# Drives.net
KiCad netlist of a schematic drawn in Altium Designer
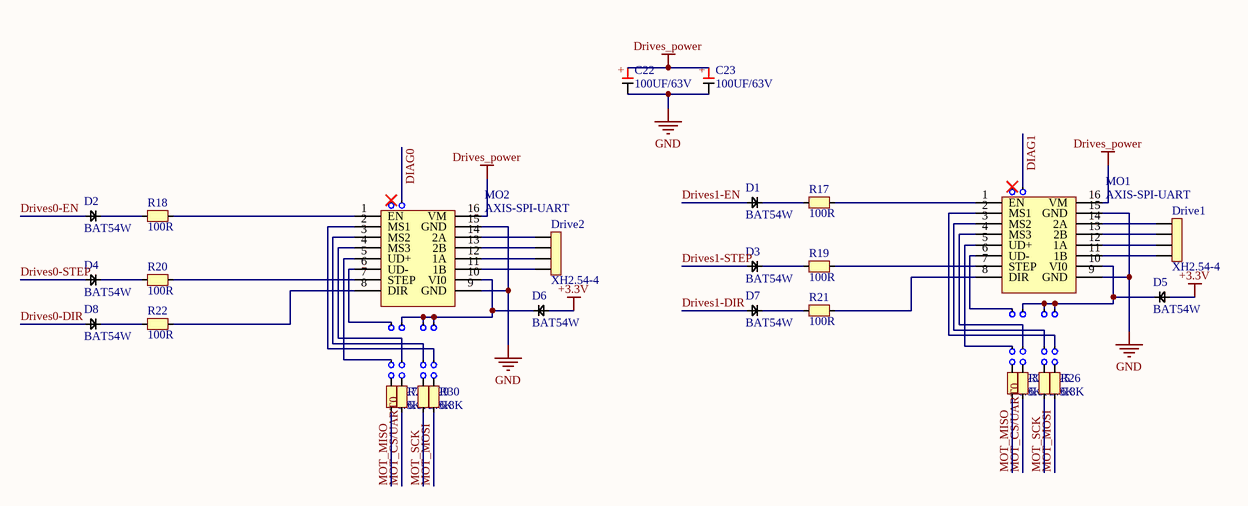
[diagram p0: Drives.SchDoc]

(export (version "E")
  (design (tool "Eeschema 10.0.6"))
  (components
    (comp (ref "C22") (value "100UF/63V") (footprint "10*10.5电解电容") (libsource (lib "jx") (part "降压电容")))
    (comp (ref "C23") (value "100UF/63V") (footprint "10*10.5电解电容") (libsource (lib "jx") (part "降压电容")))
    (comp (ref "D1")
      (value "BAT54W")
      (footprint "SOD-123")
      (description "BAT46W")
      (libsource (lib "jx") (part "Diode"))
    )
    (comp (ref "D2")
      (value "BAT54W")
      (footprint "SOD-123")
      (description "BAT46W")
      (libsource (lib "jx") (part "Diode"))
    )
    (comp (ref "D3")
      (value "BAT54W")
      (footprint "SOD-123")
      (description "BAT46W")
      (libsource (lib "jx") (part "Diode"))
    )
    (comp (ref "D4")
      (value "BAT54W")
      (footprint "SOD-123")
      (description "BAT46W")
      (libsource (lib "jx") (part "Diode"))
    )
    (comp (ref "D5")
      (value "BAT54W")
      (footprint "SOD-123")
      (description "BAT46W")
      (libsource (lib "jx") (part "Diode"))
    )
    (comp (ref "D6")
      (value "BAT54W")
      (footprint "SOD-123")
      (description "BAT46W")
      (libsource (lib "jx") (part "Diode"))
    )
    (comp (ref "D7")
      (value "BAT54W")
      (footprint "SOD-123")
      (description "BAT46W")
      (libsource (lib "jx") (part "Diode"))
    )
    (comp (ref "D8")
      (value "BAT54W")
      (footprint "SOD-123")
      (description "BAT46W")
      (libsource (lib "jx") (part "Diode"))
    )
    (comp (ref "Drive1") (value "XH2.54-4") (footprint "XH2.54-4") (libsource (lib "jx") (part "XH2.54-4")))
    (comp (ref "Drive2") (value "XH2.54-4") (footprint "XH2.54-4") (libsource (lib "jx") (part "XH2.54-4")))
    (comp (ref "MO1")
      (value "AXIS-SPI-UART")
      (footprint "AXIS-SPI-UART")
      (libsource (lib "jx") (part "AXIS-SPI-UART"))
    )
    (comp (ref "MO2")
      (value "AXIS-SPI-UART")
      (footprint "AXIS-SPI-UART")
      (libsource (lib "jx") (part "AXIS-SPI-UART"))
    )
    (comp (ref "R17") (value "100R") (footprint "0603") (libsource (lib "") (part "R_1")))
    (comp (ref "R18") (value "100R") (footprint "0603") (libsource (lib "") (part "R_1")))
    (comp (ref "R19") (value "100R") (footprint "0603") (libsource (lib "") (part "R_1")))
    (comp (ref "R20") (value "100R") (footprint "0603") (libsource (lib "") (part "R_1")))
    (comp (ref "R21") (value "100R") (footprint "0603") (libsource (lib "") (part "R_1")))
    (comp (ref "R22") (value "100R") (footprint "0603") (libsource (lib "") (part "R_1")))
    (comp (ref "R23") (value "6.8K") (footprint "0603") (libsource (lib "jx") (part "R")))
    (comp (ref "R24") (value "6.8K") (footprint "0603") (libsource (lib "jx") (part "R")))
    (comp (ref "R25") (value "6.8K") (footprint "0603") (libsource (lib "jx") (part "R")))
    (comp (ref "R26") (value "6.8K") (footprint "0603") (libsource (lib "jx") (part "R")))
    (comp (ref "R27") (value "6.8K") (footprint "0603") (libsource (lib "jx") (part "R")))
    (comp (ref "R28") (value "6.8K") (footprint "0603") (libsource (lib "jx") (part "R")))
    (comp (ref "R29") (value "6.8K") (footprint "0603") (libsource (lib "jx") (part "R")))
    (comp (ref "R30") (value "6.8K") (footprint "0603") (libsource (lib "jx") (part "R")))
  )
  (nets
    (net (code "1") (name "+3.3V") (class "Default")
      (node (ref "D5") (pin "1") (pinfunction "1_1") (pintype "passive"))
      (node (ref "D6") (pin "1") (pinfunction "1_1") (pintype "passive"))
    )
    (net (code "2") (name "/DIAG0") (class "Default")
      (node (ref "MO2") (pin "30") (pinfunction "4_30") (pintype "passive"))
    )
    (net (code "3") (name "/DIAG1") (class "Default")
      (node (ref "MO1") (pin "30") (pinfunction "4_30") (pintype "passive"))
    )
    (net (code "4") (name "/Drives0-DIR") (class "Default")
      (node (ref "D8") (pin "1") (pinfunction "1_1") (pintype "passive"))
    )
    (net (code "5") (name "/Drives0-EN") (class "Default")
      (node (ref "D2") (pin "1") (pinfunction "1_1") (pintype "passive"))
    )
    (net (code "6") (name "/Drives0-STEP") (class "Default")
      (node (ref "D4") (pin "1") (pinfunction "1_1") (pintype "passive"))
    )
    (net (code "7") (name "/Drives1-DIR") (class "Default")
      (node (ref "D7") (pin "1") (pinfunction "1_1") (pintype "passive"))
    )
    (net (code "8") (name "/Drives1-EN") (class "Default")
      (node (ref "D1") (pin "1") (pinfunction "1_1") (pintype "passive"))
    )
    (net (code "9") (name "/Drives1-STEP") (class "Default")
      (node (ref "D3") (pin "1") (pinfunction "1_1") (pintype "passive"))
    )
    (net (code "10") (name "/MOT_CS{slash}UART0") (class "Default")
      (node (ref "R24") (pin "1") (pinfunction "1_1") (pintype "passive"))
      (node (ref "R28") (pin "1") (pinfunction "1_1") (pintype "passive"))
    )
    (net (code "11") (name "/MOT_MISO") (class "Default")
      (node (ref "R23") (pin "1") (pinfunction "1_1") (pintype "passive"))
      (node (ref "R27") (pin "1") (pinfunction "1_1") (pintype "passive"))
    )
    (net (code "12") (name "/MOT_MOSI") (class "Default")
      (node (ref "R26") (pin "1") (pinfunction "1_1") (pintype "passive"))
      (node (ref "R30") (pin "1") (pinfunction "1_1") (pintype "passive"))
    )
    (net (code "13") (name "/MOT_SCK") (class "Default")
      (node (ref "R25") (pin "1") (pinfunction "1_1") (pintype "passive"))
      (node (ref "R29") (pin "1") (pinfunction "1_1") (pintype "passive"))
    )
    (net (code "14") (name "Drives_power") (class "Default")
      (node (ref "C22") (pin "1") (pinfunction "1_1") (pintype "passive"))
      (node (ref "C23") (pin "1") (pinfunction "1_1") (pintype "passive"))
      (node (ref "MO1") (pin "16") (pinfunction "VM_16") (pintype "passive"))
      (node (ref "MO2") (pin "16") (pinfunction "VM_16") (pintype "passive"))
    )
    (net (code "15") (name "GND") (class "Default")
      (node (ref "C22") (pin "2") (pinfunction "2_2") (pintype "passive"))
      (node (ref "C23") (pin "2") (pinfunction "2_2") (pintype "passive"))
      (node (ref "MO1") (pin "15") (pinfunction "GND_15") (pintype "passive"))
      (node (ref "MO1") (pin "9") (pinfunction "GND_9") (pintype "passive"))
      (node (ref "MO2") (pin "15") (pinfunction "GND_15") (pintype "passive"))
      (node (ref "MO2") (pin "9") (pinfunction "GND_9") (pintype "passive"))
    )
    (net (code "16") (name "Net-(D1-Pad2)") (class "Default")
      (node (ref "D1") (pin "2") (pinfunction "2_2") (pintype "passive"))
      (node (ref "R17") (pin "2") (pinfunction "2_2") (pintype "passive"))
    )
    (net (code "17") (name "Net-(D2-Pad2)") (class "Default")
      (node (ref "D2") (pin "2") (pinfunction "2_2") (pintype "passive"))
      (node (ref "R18") (pin "2") (pinfunction "2_2") (pintype "passive"))
    )
    (net (code "18") (name "Net-(D3-Pad2)") (class "Default")
      (node (ref "D3") (pin "2") (pinfunction "2_2") (pintype "passive"))
      (node (ref "R19") (pin "2") (pinfunction "2_2") (pintype "passive"))
    )
    (net (code "19") (name "Net-(D4-Pad2)") (class "Default")
      (node (ref "D4") (pin "2") (pinfunction "2_2") (pintype "passive"))
      (node (ref "R20") (pin "2") (pinfunction "2_2") (pintype "passive"))
    )
    (net (code "20") (name "Net-(D7-Pad2)") (class "Default")
      (node (ref "D7") (pin "2") (pinfunction "2_2") (pintype "passive"))
      (node (ref "R21") (pin "2") (pinfunction "2_2") (pintype "passive"))
    )
    (net (code "21") (name "Net-(D8-Pad2)") (class "Default")
      (node (ref "D8") (pin "2") (pinfunction "2_2") (pintype "passive"))
      (node (ref "R22") (pin "2") (pinfunction "2_2") (pintype "passive"))
    )
    (net (code "22") (name "Net-(MO1-1A)") (class "Default")
      (node (ref "Drive1") (pin "3") (pinfunction "3_3") (pintype "passive"))
      (node (ref "MO1") (pin "12") (pinfunction "1A_12") (pintype "passive"))
    )
    (net (code "23") (name "Net-(MO1-1B)") (class "Default")
      (node (ref "Drive1") (pin "4") (pinfunction "4_4") (pintype "passive"))
      (node (ref "MO1") (pin "11") (pinfunction "1B_11") (pintype "passive"))
    )
    (net (code "24") (name "Net-(MO1-2-Pad25)") (class "Default")
      (node (ref "MO1") (pin "25") (pinfunction "2_25") (pintype "passive"))
      (node (ref "R25") (pin "2") (pinfunction "2_2") (pintype "passive"))
    )
    (net (code "25") (name "Net-(MO1-2A)") (class "Default")
      (node (ref "Drive1") (pin "1") (pinfunction "1_1") (pintype "passive"))
      (node (ref "MO1") (pin "14") (pinfunction "2A_14") (pintype "passive"))
    )
    (net (code "26") (name "Net-(MO1-2B)") (class "Default")
      (node (ref "Drive1") (pin "2") (pinfunction "2_2") (pintype "passive"))
      (node (ref "MO1") (pin "13") (pinfunction "2B_13") (pintype "passive"))
    )
    (net (code "27") (name "Net-(MO1-3-Pad19)") (class "Default")
      (node (ref "MO1") (pin "19") (pinfunction "3_19") (pintype "passive"))
      (node (ref "R23") (pin "2") (pinfunction "2_2") (pintype "passive"))
    )
    (net (code "28") (name "Net-(MO1-4-Pad20)") (class "Default")
      (node (ref "MO1") (pin "20") (pinfunction "4_20") (pintype "passive"))
      (node (ref "R24") (pin "2") (pinfunction "2_2") (pintype "passive"))
    )
    (net (code "29") (name "Net-(MO1-5-Pad26)") (class "Default")
      (node (ref "MO1") (pin "26") (pinfunction "5_26") (pintype "passive"))
      (node (ref "R26") (pin "2") (pinfunction "2_2") (pintype "passive"))
    )
    (net (code "30") (name "Net-(MO1-DIR)") (class "Default")
      (node (ref "MO1") (pin "8") (pinfunction "DIR_8") (pintype "passive"))
      (node (ref "R21") (pin "1") (pinfunction "1_1") (pintype "passive"))
    )
    (net (code "31") (name "Net-(MO1-EN)") (class "Default")
      (node (ref "MO1") (pin "1") (pinfunction "EN_1") (pintype "passive"))
      (node (ref "R17") (pin "1") (pinfunction "1_1") (pintype "passive"))
    )
    (net (code "32") (name "Net-(MO1-MS1)") (class "Default")
      (node (ref "MO1") (pin "2") (pinfunction "MS1_2") (pintype "passive"))
      (node (ref "MO1") (pin "27") (pinfunction "6_27") (pintype "passive"))
    )
    (net (code "33") (name "Net-(MO1-MS2)") (class "Default")
      (node (ref "MO1") (pin "24") (pinfunction "1_24") (pintype "passive"))
      (node (ref "MO1") (pin "3") (pinfunction "MS2_3") (pintype "passive"))
    )
    (net (code "34") (name "Net-(MO1-MS3)") (class "Default")
      (node (ref "MO1") (pin "21") (pinfunction "5_21") (pintype "passive"))
      (node (ref "MO1") (pin "4") (pinfunction "MS3_4") (pintype "passive"))
    )
    (net (code "35") (name "Net-(MO1-STEP)") (class "Default")
      (node (ref "MO1") (pin "7") (pinfunction "STEP_7") (pintype "passive"))
      (node (ref "R19") (pin "1") (pinfunction "1_1") (pintype "passive"))
    )
    (net (code "36") (name "Net-(MO1-UD+)") (class "Default")
      (node (ref "MO1") (pin "18") (pinfunction "2_18") (pintype "passive"))
      (node (ref "MO1") (pin "5") (pinfunction "UD+_5") (pintype "passive"))
    )
    (net (code "37") (name "Net-(MO1-UD-)") (class "Default")
      (node (ref "MO1") (pin "17") (pinfunction "1_17") (pintype "passive"))
      (node (ref "MO1") (pin "6") (pinfunction "UD-_6") (pintype "passive"))
    )
    (net (code "38") (name "Net-(MO1-VI0)") (class "Default")
      (node (ref "D5") (pin "2") (pinfunction "2_2") (pintype "passive"))
      (node (ref "MO1") (pin "10") (pinfunction "VI0_10") (pintype "passive"))
      (node (ref "MO1") (pin "22") (pinfunction "6_22") (pintype "passive"))
      (node (ref "MO1") (pin "23") (pinfunction "3_23") (pintype "passive"))
      (node (ref "MO1") (pin "28") (pinfunction "4_28") (pintype "passive"))
    )
    (net (code "39") (name "Net-(MO2-1A)") (class "Default")
      (node (ref "Drive2") (pin "3") (pinfunction "3_3") (pintype "passive"))
      (node (ref "MO2") (pin "12") (pinfunction "1A_12") (pintype "passive"))
    )
    (net (code "40") (name "Net-(MO2-1B)") (class "Default")
      (node (ref "Drive2") (pin "4") (pinfunction "4_4") (pintype "passive"))
      (node (ref "MO2") (pin "11") (pinfunction "1B_11") (pintype "passive"))
    )
    (net (code "41") (name "Net-(MO2-2-Pad25)") (class "Default")
      (node (ref "MO2") (pin "25") (pinfunction "2_25") (pintype "passive"))
      (node (ref "R29") (pin "2") (pinfunction "2_2") (pintype "passive"))
    )
    (net (code "42") (name "Net-(MO2-2A)") (class "Default")
      (node (ref "Drive2") (pin "1") (pinfunction "1_1") (pintype "passive"))
      (node (ref "MO2") (pin "14") (pinfunction "2A_14") (pintype "passive"))
    )
    (net (code "43") (name "Net-(MO2-2B)") (class "Default")
      (node (ref "Drive2") (pin "2") (pinfunction "2_2") (pintype "passive"))
      (node (ref "MO2") (pin "13") (pinfunction "2B_13") (pintype "passive"))
    )
    (net (code "44") (name "Net-(MO2-3-Pad19)") (class "Default")
      (node (ref "MO2") (pin "19") (pinfunction "3_19") (pintype "passive"))
      (node (ref "R27") (pin "2") (pinfunction "2_2") (pintype "passive"))
    )
    (net (code "45") (name "Net-(MO2-4-Pad20)") (class "Default")
      (node (ref "MO2") (pin "20") (pinfunction "4_20") (pintype "passive"))
      (node (ref "R28") (pin "2") (pinfunction "2_2") (pintype "passive"))
    )
    (net (code "46") (name "Net-(MO2-5-Pad26)") (class "Default")
      (node (ref "MO2") (pin "26") (pinfunction "5_26") (pintype "passive"))
      (node (ref "R30") (pin "2") (pinfunction "2_2") (pintype "passive"))
    )
    (net (code "47") (name "Net-(MO2-DIR)") (class "Default")
      (node (ref "MO2") (pin "8") (pinfunction "DIR_8") (pintype "passive"))
      (node (ref "R22") (pin "1") (pinfunction "1_1") (pintype "passive"))
    )
    (net (code "48") (name "Net-(MO2-EN)") (class "Default")
      (node (ref "MO2") (pin "1") (pinfunction "EN_1") (pintype "passive"))
      (node (ref "R18") (pin "1") (pinfunction "1_1") (pintype "passive"))
    )
    (net (code "49") (name "Net-(MO2-MS1)") (class "Default")
      (node (ref "MO2") (pin "2") (pinfunction "MS1_2") (pintype "passive"))
      (node (ref "MO2") (pin "27") (pinfunction "6_27") (pintype "passive"))
    )
    (net (code "50") (name "Net-(MO2-MS2)") (class "Default")
      (node (ref "MO2") (pin "24") (pinfunction "1_24") (pintype "passive"))
      (node (ref "MO2") (pin "3") (pinfunction "MS2_3") (pintype "passive"))
    )
    (net (code "51") (name "Net-(MO2-MS3)") (class "Default")
      (node (ref "MO2") (pin "21") (pinfunction "5_21") (pintype "passive"))
      (node (ref "MO2") (pin "4") (pinfunction "MS3_4") (pintype "passive"))
    )
    (net (code "52") (name "Net-(MO2-STEP)") (class "Default")
      (node (ref "MO2") (pin "7") (pinfunction "STEP_7") (pintype "passive"))
      (node (ref "R20") (pin "1") (pinfunction "1_1") (pintype "passive"))
    )
    (net (code "53") (name "Net-(MO2-UD+)") (class "Default")
      (node (ref "MO2") (pin "18") (pinfunction "2_18") (pintype "passive"))
      (node (ref "MO2") (pin "5") (pinfunction "UD+_5") (pintype "passive"))
    )
    (net (code "54") (name "Net-(MO2-UD-)") (class "Default")
      (node (ref "MO2") (pin "17") (pinfunction "1_17") (pintype "passive"))
      (node (ref "MO2") (pin "6") (pinfunction "UD-_6") (pintype "passive"))
    )
    (net (code "55") (name "Net-(MO2-VI0)") (class "Default")
      (node (ref "D6") (pin "2") (pinfunction "2_2") (pintype "passive"))
      (node (ref "MO2") (pin "10") (pinfunction "VI0_10") (pintype "passive"))
      (node (ref "MO2") (pin "22") (pinfunction "6_22") (pintype "passive"))
      (node (ref "MO2") (pin "23") (pinfunction "3_23") (pintype "passive"))
      (node (ref "MO2") (pin "28") (pinfunction "4_28") (pintype "passive"))
    )
    (net (code "56") (name "unconnected-(MO1-3-Pad29)") (class "Default")
      (node (ref "MO1") (pin "29") (pinfunction "3_29") (pintype "passive+no_connect"))
    )
    (net (code "57") (name "unconnected-(MO2-3-Pad29)") (class "Default")
      (node (ref "MO2") (pin "29") (pinfunction "3_29") (pintype "passive+no_connect"))
    )
  )
)
